# packmonitor.net
KiCad netlist of a schematic drawn in EAGLE
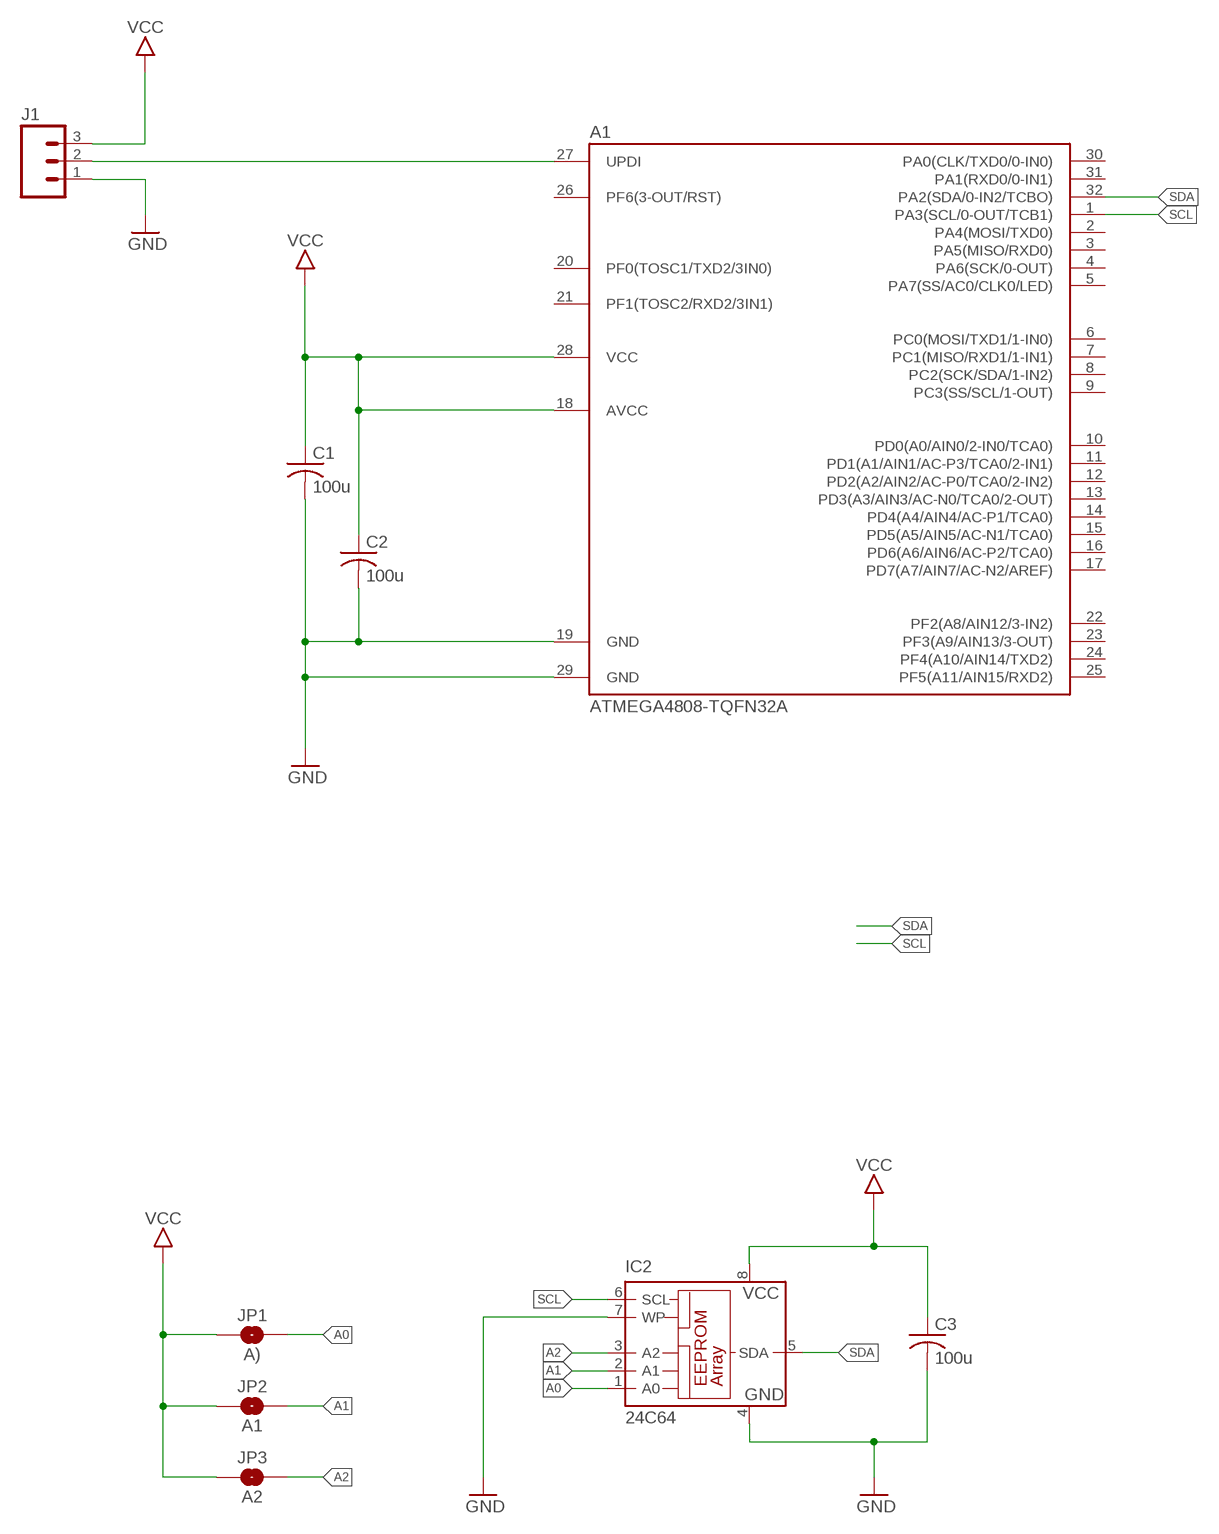
[diagram p0: schematic, sheet 1]

(export (version "E")
  (design (tool "Eeschema 10.0.6"))
  (components
    (comp (ref "A1")
      (value "ATMEGA4808-TQFN32A")
      (footprint "eagle-import:TQFP32-08")
      (libsource (lib "eagle-import") (part "ATMEGA4808-TQFN32A"))
    )
    (comp (ref "C1")
      (value "100u")
      (footprint "eagle-import:C0603")
      (libsource (lib "eagle-import") (part "C-USC0603"))
    )
    (comp (ref "C2")
      (value "100u")
      (footprint "eagle-import:C0603")
      (libsource (lib "eagle-import") (part "C-USC0603"))
    )
    (comp (ref "C3")
      (value "100u")
      (footprint "eagle-import:C0603")
      (libsource (lib "eagle-import") (part "C-USC0603"))
    )
    (comp (ref "IC2")
      (value "24C64")
      (footprint "eagle-import:SO-08")
      (libsource (lib "eagle-import") (part "24CSN04C"))
    )
    (comp (ref "J1")
      (value "M03LOCK_LONGPADS")
      (footprint "eagle-import:1X03_LOCK_LONGPADS")
      (libsource (lib "eagle-import") (part "M03LOCK_LONGPADS"))
    )
    (comp (ref "JP1")
      (value "A)")
      (footprint "eagle-import:SMT-JUMPER_2_NO_SILK")
      (libsource (lib "eagle-import") (part "JUMPER-SMT_2_NO_SILK"))
    )
    (comp (ref "JP2")
      (value "A1")
      (footprint "eagle-import:SMT-JUMPER_2_NO_SILK")
      (libsource (lib "eagle-import") (part "JUMPER-SMT_2_NO_SILK"))
    )
    (comp (ref "JP3")
      (value "A2")
      (footprint "eagle-import:SMT-JUMPER_2_NO_SILK")
      (libsource (lib "eagle-import") (part "JUMPER-SMT_2_NO_SILK"))
    )
  )
  (nets
    (net (code "1") (name "A0") (class "Default")
      (node (ref "IC2") (pin "1") (pinfunction "A0_1") (pintype "input"))
      (node (ref "JP1") (pin "2") (pinfunction "2_2") (pintype "passive"))
    )
    (net (code "2") (name "A1") (class "Default")
      (node (ref "IC2") (pin "2") (pinfunction "A1_2") (pintype "input"))
      (node (ref "JP2") (pin "2") (pinfunction "2_2") (pintype "passive"))
    )
    (net (code "3") (name "A2") (class "Default")
      (node (ref "IC2") (pin "3") (pinfunction "A2_3") (pintype "input"))
      (node (ref "JP3") (pin "2") (pinfunction "2_2") (pintype "passive"))
    )
    (net (code "4") (name "GND") (class "Default")
      (node (ref "A1") (pin "19") (pinfunction "GND_19") (pintype "power_in"))
      (node (ref "A1") (pin "29") (pinfunction "GND_29") (pintype "power_in"))
      (node (ref "C1") (pin "2") (pinfunction "2_2") (pintype "passive"))
      (node (ref "C2") (pin "2") (pinfunction "2_2") (pintype "passive"))
      (node (ref "C3") (pin "2") (pinfunction "2_2") (pintype "passive"))
      (node (ref "IC2") (pin "4") (pinfunction "GND_4") (pintype "power_in"))
      (node (ref "IC2") (pin "7") (pinfunction "WP_7") (pintype "input"))
      (node (ref "J1") (pin "1") (pinfunction "1_1") (pintype "passive"))
    )
    (net (code "5") (name "Net-(A1-UPDI)") (class "Default")
      (node (ref "A1") (pin "27") (pinfunction "UPDI_27") (pintype "bidirectional"))
      (node (ref "J1") (pin "2") (pinfunction "2_2") (pintype "passive"))
    )
    (net (code "6") (name "SCL") (class "Default")
      (node (ref "A1") (pin "1") (pinfunction "PA3(SCL/0-OUT/TCB1)_1") (pintype "bidirectional"))
      (node (ref "IC2") (pin "6") (pinfunction "SCL_6") (pintype "input"))
    )
    (net (code "7") (name "SDA") (class "Default")
      (node (ref "A1") (pin "32") (pinfunction "PA2(SDA/0-IN2/TCBO)_32") (pintype "bidirectional"))
      (node (ref "IC2") (pin "5") (pinfunction "SDA_5") (pintype "bidirectional"))
    )
    (net (code "8") (name "VCC") (class "Default")
      (node (ref "A1") (pin "18") (pinfunction "AVCC_18") (pintype "passive"))
      (node (ref "A1") (pin "28") (pinfunction "VCC_28") (pintype "power_in"))
      (node (ref "C1") (pin "1") (pinfunction "1_1") (pintype "passive"))
      (node (ref "C2") (pin "1") (pinfunction "1_1") (pintype "passive"))
      (node (ref "C3") (pin "1") (pinfunction "1_1") (pintype "passive"))
      (node (ref "IC2") (pin "8") (pinfunction "VCC_8") (pintype "power_in"))
      (node (ref "J1") (pin "3") (pinfunction "3_3") (pintype "passive"))
      (node (ref "JP1") (pin "1") (pinfunction "1_1") (pintype "passive"))
      (node (ref "JP2") (pin "1") (pinfunction "1_1") (pintype "passive"))
      (node (ref "JP3") (pin "1") (pinfunction "1_1") (pintype "passive"))
    )
    (net (code "9") (name "unconnected-(A1-PA0(CLK{slash}TXD0{slash}0-IN0)-Pad30)") (class "Default")
      (node (ref "A1") (pin "30") (pinfunction "PA0(CLK/TXD0/0-IN0)_30") (pintype "bidirectional"))
    )
    (net (code "10") (name "unconnected-(A1-PA1(RXD0{slash}0-IN1)-Pad31)") (class "Default")
      (node (ref "A1") (pin "31") (pinfunction "PA1(RXD0/0-IN1)_31") (pintype "bidirectional"))
    )
    (net (code "11") (name "unconnected-(A1-PA4(MOSI{slash}TXD0)-Pad2)") (class "Default")
      (node (ref "A1") (pin "2") (pinfunction "PA4(MOSI/TXD0)_2") (pintype "bidirectional"))
    )
    (net (code "12") (name "unconnected-(A1-PA5(MISO{slash}RXD0)-Pad3)") (class "Default")
      (node (ref "A1") (pin "3") (pinfunction "PA5(MISO/RXD0)_3") (pintype "bidirectional"))
    )
    (net (code "13") (name "unconnected-(A1-PA6(SCK{slash}0-OUT)-Pad4)") (class "Default")
      (node (ref "A1") (pin "4") (pinfunction "PA6(SCK/0-OUT)_4") (pintype "bidirectional"))
    )
    (net (code "14") (name "unconnected-(A1-PA7(SS{slash}AC0{slash}CLK0{slash}LED)-Pad5)") (class "Default")
      (node (ref "A1") (pin "5") (pinfunction "PA7(SS/AC0/CLK0/LED)_5") (pintype "bidirectional"))
    )
    (net (code "15") (name "unconnected-(A1-PC0(MOSI{slash}TXD1{slash}1-IN0)-Pad6)") (class "Default")
      (node (ref "A1") (pin "6") (pinfunction "PC0(MOSI/TXD1/1-IN0)_6") (pintype "bidirectional"))
    )
    (net (code "16") (name "unconnected-(A1-PC1(MISO{slash}RXD1{slash}1-IN1)-Pad7)") (class "Default")
      (node (ref "A1") (pin "7") (pinfunction "PC1(MISO/RXD1/1-IN1)_7") (pintype "bidirectional"))
    )
    (net (code "17") (name "unconnected-(A1-PC2(SCK{slash}SDA{slash}1-IN2)-Pad8)") (class "Default")
      (node (ref "A1") (pin "8") (pinfunction "PC2(SCK/SDA/1-IN2)_8") (pintype "bidirectional"))
    )
    (net (code "18") (name "unconnected-(A1-PC3(SS{slash}SCL{slash}1-OUT)-Pad9)") (class "Default")
      (node (ref "A1") (pin "9") (pinfunction "PC3(SS/SCL/1-OUT)_9") (pintype "bidirectional"))
    )
    (net (code "19") (name "unconnected-(A1-PD0(A0{slash}AIN0{slash}2-IN0{slash}TCA0)-Pad10)") (class "Default")
      (node (ref "A1") (pin "10") (pinfunction "PD0(A0/AIN0/2-IN0/TCA0)_10") (pintype "bidirectional"))
    )
    (net (code "20") (name "unconnected-(A1-PD1(A1{slash}AIN1{slash}AC-P3{slash}TCA0{slash}2-IN1)-Pad11)") (class "Default")
      (node (ref "A1") (pin "11") (pinfunction "PD1(A1/AIN1/AC-P3/TCA0/2-IN1)_11") (pintype "bidirectional"))
    )
    (net (code "21") (name "unconnected-(A1-PD2(A2{slash}AIN2{slash}AC-P0{slash}TCA0{slash}2-IN2)-Pad12)") (class "Default")
      (node (ref "A1") (pin "12") (pinfunction "PD2(A2/AIN2/AC-P0/TCA0/2-IN2)_12") (pintype "bidirectional"))
    )
    (net (code "22") (name "unconnected-(A1-PD3(A3{slash}AIN3{slash}AC-N0{slash}TCA0{slash}2-OUT)-Pad13)") (class "Default")
      (node (ref "A1") (pin "13") (pinfunction "PD3(A3/AIN3/AC-N0/TCA0/2-OUT)_13") (pintype "bidirectional"))
    )
    (net (code "23") (name "unconnected-(A1-PD4(A4{slash}AIN4{slash}AC-P1{slash}TCA0)-Pad14)") (class "Default")
      (node (ref "A1") (pin "14") (pinfunction "PD4(A4/AIN4/AC-P1/TCA0)_14") (pintype "bidirectional"))
    )
    (net (code "24") (name "unconnected-(A1-PD5(A5{slash}AIN5{slash}AC-N1{slash}TCA0)-Pad15)") (class "Default")
      (node (ref "A1") (pin "15") (pinfunction "PD5(A5/AIN5/AC-N1/TCA0)_15") (pintype "bidirectional"))
    )
    (net (code "25") (name "unconnected-(A1-PD6(A6{slash}AIN6{slash}AC-P2{slash}TCA0)-Pad16)") (class "Default")
      (node (ref "A1") (pin "16") (pinfunction "PD6(A6/AIN6/AC-P2/TCA0)_16") (pintype "bidirectional"))
    )
    (net (code "26") (name "unconnected-(A1-PD7(A7{slash}AIN7{slash}AC-N2{slash}AREF)-Pad17)") (class "Default")
      (node (ref "A1") (pin "17") (pinfunction "PD7(A7/AIN7/AC-N2/AREF)_17") (pintype "bidirectional"))
    )
    (net (code "27") (name "unconnected-(A1-PF0(TOSC1{slash}TXD2{slash}3IN0)-Pad20)") (class "Default")
      (node (ref "A1") (pin "20") (pinfunction "PF0(TOSC1/TXD2/3IN0)_20") (pintype "bidirectional"))
    )
    (net (code "28") (name "unconnected-(A1-PF1(TOSC2{slash}RXD2{slash}3IN1)-Pad21)") (class "Default")
      (node (ref "A1") (pin "21") (pinfunction "PF1(TOSC2/RXD2/3IN1)_21") (pintype "bidirectional"))
    )
    (net (code "29") (name "unconnected-(A1-PF2(A8{slash}AIN12{slash}3-IN2)-Pad22)") (class "Default")
      (node (ref "A1") (pin "22") (pinfunction "PF2(A8/AIN12/3-IN2)_22") (pintype "bidirectional"))
    )
    (net (code "30") (name "unconnected-(A1-PF3(A9{slash}AIN13{slash}3-OUT)-Pad23)") (class "Default")
      (node (ref "A1") (pin "23") (pinfunction "PF3(A9/AIN13/3-OUT)_23") (pintype "bidirectional"))
    )
    (net (code "31") (name "unconnected-(A1-PF4(A10{slash}AIN14{slash}TXD2)-Pad24)") (class "Default")
      (node (ref "A1") (pin "24") (pinfunction "PF4(A10/AIN14/TXD2)_24") (pintype "bidirectional"))
    )
    (net (code "32") (name "unconnected-(A1-PF5(A11{slash}AIN15{slash}RXD2)-Pad25)") (class "Default")
      (node (ref "A1") (pin "25") (pinfunction "PF5(A11/AIN15/RXD2)_25") (pintype "bidirectional"))
    )
    (net (code "33") (name "unconnected-(A1-PF6(3-OUT{slash}RST)-Pad26)") (class "Default")
      (node (ref "A1") (pin "26") (pinfunction "PF6(3-OUT/RST)_26") (pintype "bidirectional"))
    )
  )
)
